# PHY_ETHERNET.net
KiCad netlist of a schematic drawn in Altium Designer
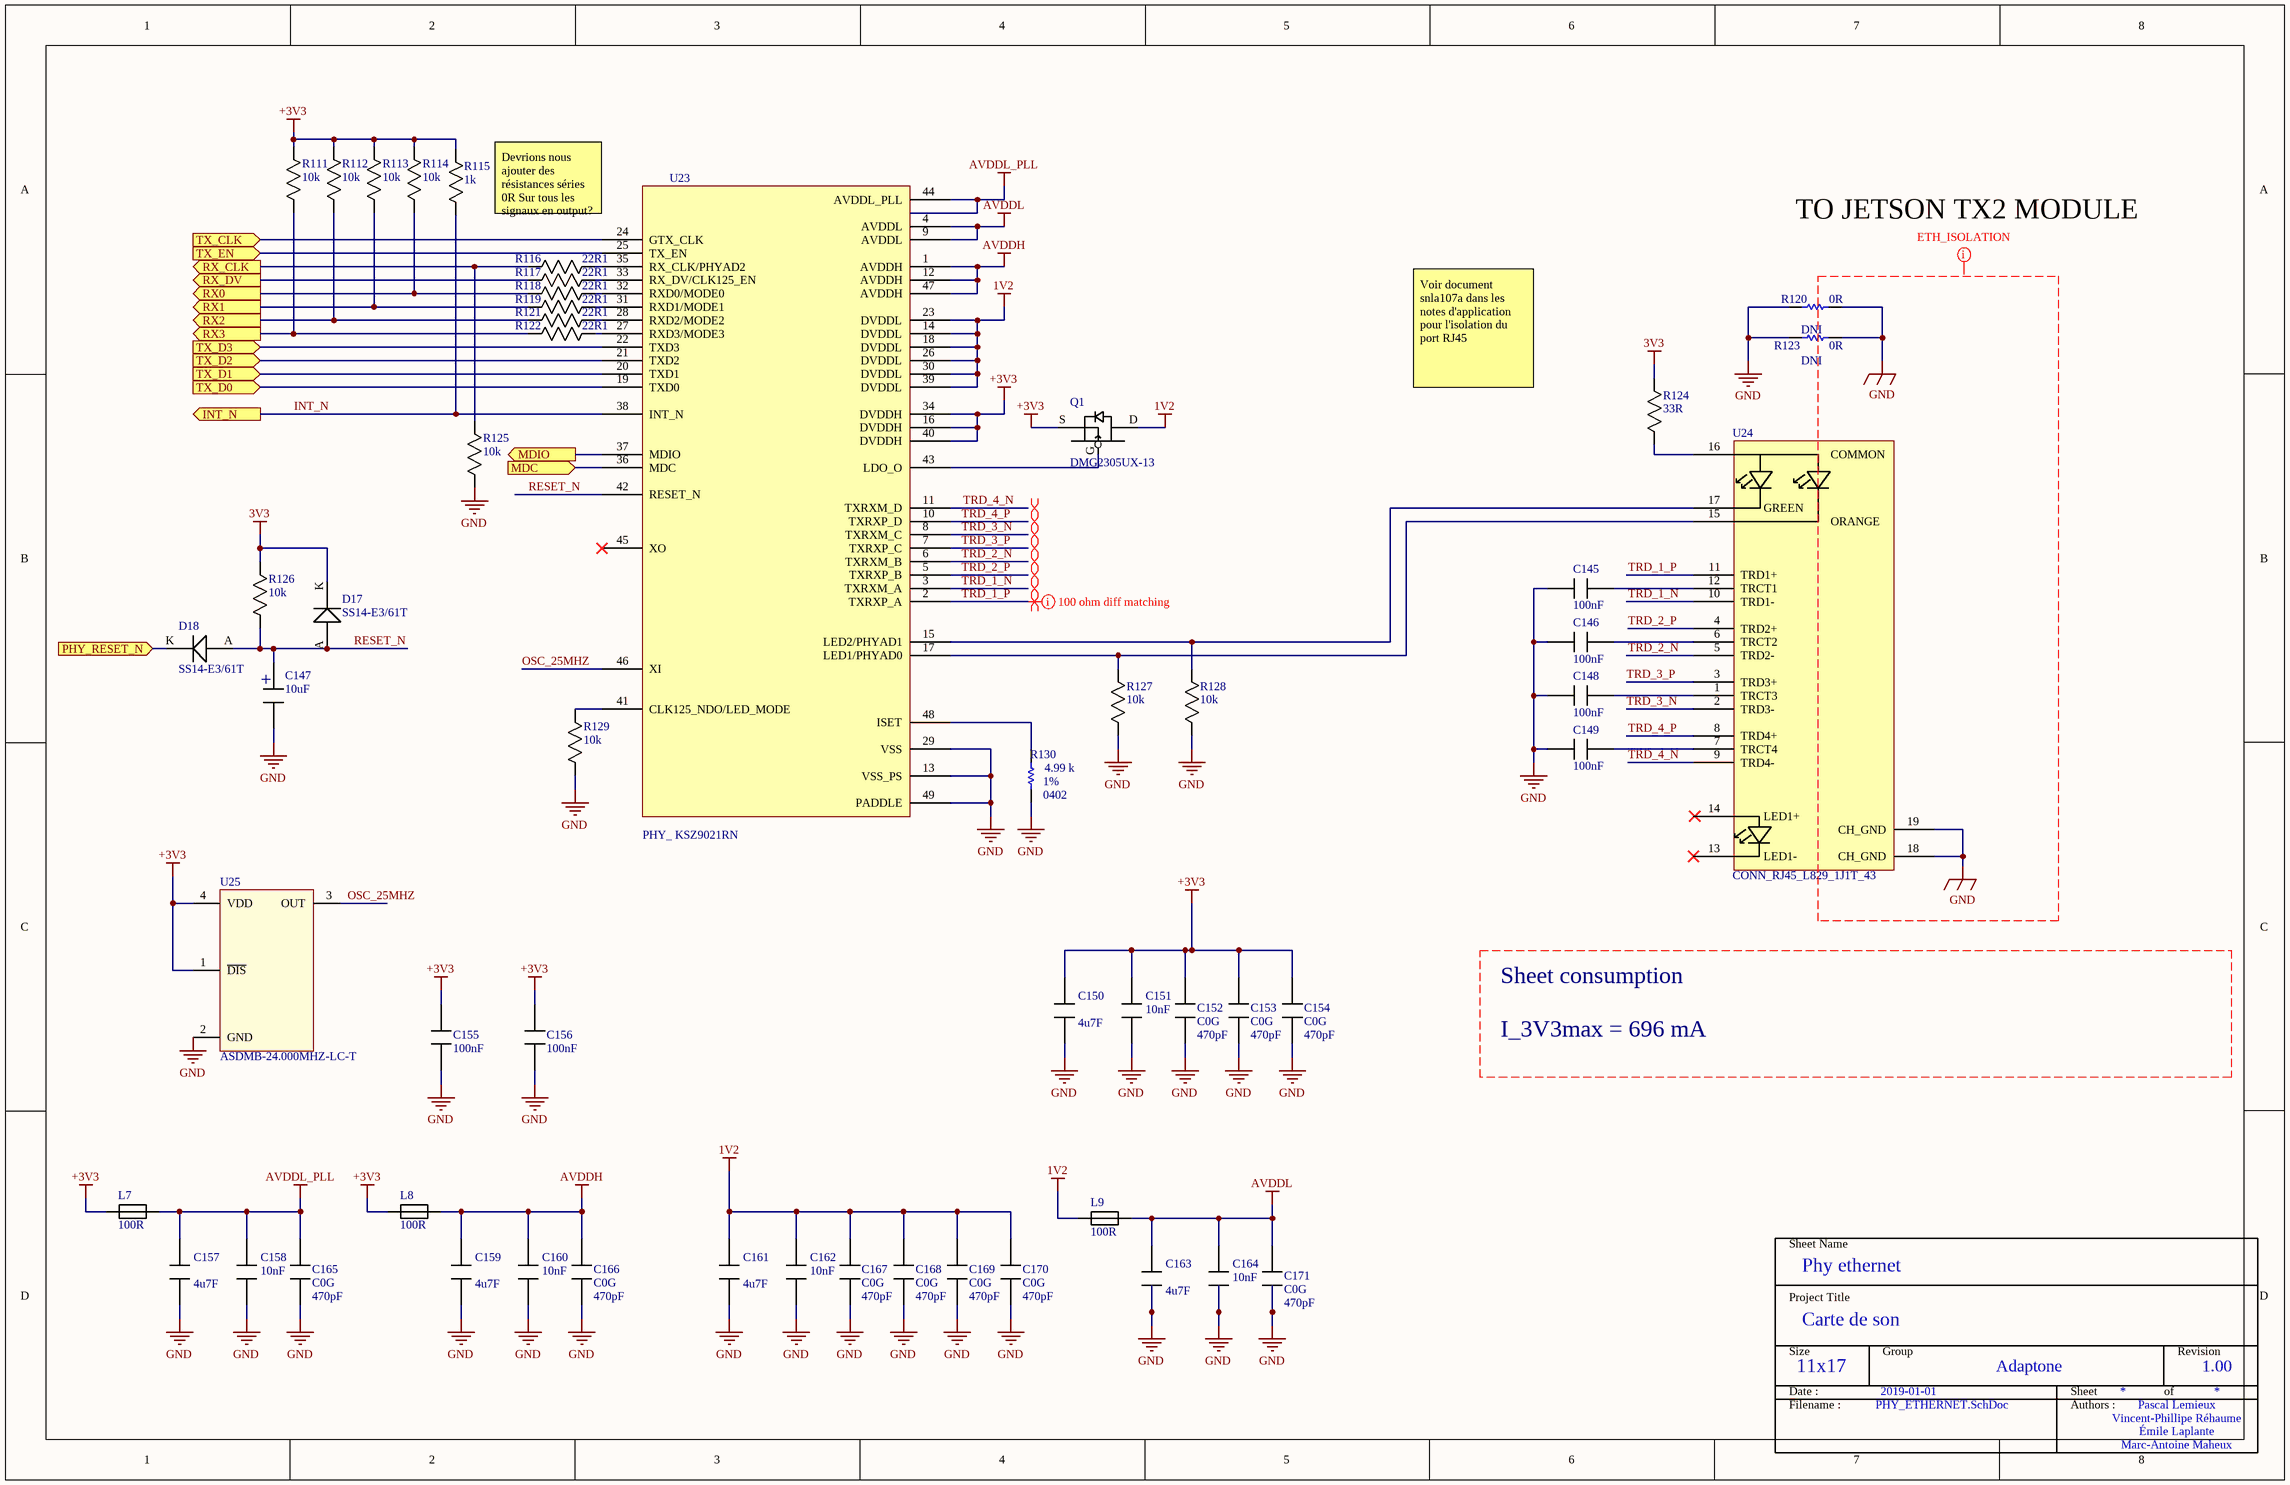
[diagram p0: PHY_ETHERNET.SchDoc]

(export (version "E")
  (design (tool "Eeschema 10.0.6"))
  (components
    (comp (ref "C145")
      (value "100nF")
      (footprint "0603")
      (description "Capacitor")
      (fields (field (name "MFG") "Samsung"))
      (libsource (lib "ADAPTONE_CARTE_DE_SON") (part "Capacitor"))
    )
    (comp (ref "C146")
      (value "100nF")
      (footprint "0603")
      (description "Capacitor")
      (fields (field (name "MFG") "Samsung"))
      (libsource (lib "ADAPTONE_CARTE_DE_SON") (part "Capacitor"))
    )
    (comp (ref "C147")
      (value "10uF")
      (footprint "CAP_RAD_SMD_DIA157")
      (description "Capacitor")
      (fields (field (name "MFG") "Nichicon") (field (name "Comment") "Capacitor_Polarized"))
      (libsource (lib "ADAPTONE_CARTE_DE_SON") (part "Capacitor_Polarized"))
    )
    (comp (ref "C148")
      (value "100nF")
      (footprint "0603")
      (description "Capacitor")
      (fields (field (name "MFG") "Samsung"))
      (libsource (lib "ADAPTONE_CARTE_DE_SON") (part "Capacitor"))
    )
    (comp (ref "C149")
      (value "100nF")
      (footprint "0603")
      (description "Capacitor")
      (fields (field (name "MFG") "Samsung"))
      (libsource (lib "ADAPTONE_CARTE_DE_SON") (part "Capacitor"))
    )
    (comp (ref "C150")
      (value "4u7F")
      (footprint "0805")
      (description "Capacitor")
      (fields (field (name "MFG") "Samsung"))
      (libsource (lib "ADAPTONE_CARTE_DE_SON") (part "Capacitor"))
    )
    (comp (ref "C151")
      (value "10nF")
      (footprint "0603")
      (description "Capacitor")
      (fields (field (name "MFG") "Murata"))
      (libsource (lib "ADAPTONE_CARTE_DE_SON") (part "Capacitor"))
    )
    (comp (ref "C152")
      (value "470pF")
      (footprint "0603")
      (description "Capacitor")
      (fields (field (name "MFG") "Samsung") (field (name "TYPE") "C0G"))
      (libsource (lib "ADAPTONE_CARTE_DE_SON") (part "Capacitor"))
    )
    (comp (ref "C153")
      (value "470pF")
      (footprint "0603")
      (description "Capacitor")
      (fields (field (name "MFG") "Samsung") (field (name "TYPE") "C0G"))
      (libsource (lib "ADAPTONE_CARTE_DE_SON") (part "Capacitor"))
    )
    (comp (ref "C154")
      (value "470pF")
      (footprint "0603")
      (description "Capacitor")
      (fields (field (name "MFG") "Samsung") (field (name "TYPE") "C0G"))
      (libsource (lib "ADAPTONE_CARTE_DE_SON") (part "Capacitor"))
    )
    (comp (ref "C155")
      (value "100nF")
      (footprint "0603")
      (description "Capacitor")
      (fields (field (name "MFG") "Samsung"))
      (libsource (lib "ADAPTONE_CARTE_DE_SON") (part "Capacitor"))
    )
    (comp (ref "C156")
      (value "100nF")
      (footprint "0603")
      (description "Capacitor")
      (fields (field (name "MFG") "Samsung"))
      (libsource (lib "ADAPTONE_CARTE_DE_SON") (part "Capacitor"))
    )
    (comp (ref "C157")
      (value "4u7F")
      (footprint "0805")
      (description "Capacitor")
      (fields (field (name "MFG") "Samsung"))
      (libsource (lib "ADAPTONE_CARTE_DE_SON") (part "Capacitor"))
    )
    (comp (ref "C158")
      (value "10nF")
      (footprint "0603")
      (description "Capacitor")
      (fields (field (name "MFG") "Murata"))
      (libsource (lib "ADAPTONE_CARTE_DE_SON") (part "Capacitor"))
    )
    (comp (ref "C159")
      (value "4u7F")
      (footprint "0805")
      (description "Capacitor")
      (fields (field (name "MFG") "Samsung"))
      (libsource (lib "ADAPTONE_CARTE_DE_SON") (part "Capacitor"))
    )
    (comp (ref "C160")
      (value "10nF")
      (footprint "0603")
      (description "Capacitor")
      (fields (field (name "MFG") "Murata"))
      (libsource (lib "ADAPTONE_CARTE_DE_SON") (part "Capacitor"))
    )
    (comp (ref "C161")
      (value "4u7F")
      (footprint "0805")
      (description "Capacitor")
      (fields (field (name "MFG") "Samsung"))
      (libsource (lib "ADAPTONE_CARTE_DE_SON") (part "Capacitor"))
    )
    (comp (ref "C162")
      (value "10nF")
      (footprint "0603")
      (description "Capacitor")
      (fields (field (name "MFG") "Murata"))
      (libsource (lib "ADAPTONE_CARTE_DE_SON") (part "Capacitor"))
    )
    (comp (ref "C163")
      (value "4u7F")
      (footprint "0805")
      (description "Capacitor")
      (fields (field (name "MFG") "Samsung"))
      (libsource (lib "ADAPTONE_CARTE_DE_SON") (part "Capacitor"))
    )
    (comp (ref "C164")
      (value "10nF")
      (footprint "0603")
      (description "Capacitor")
      (fields (field (name "MFG") "Murata"))
      (libsource (lib "ADAPTONE_CARTE_DE_SON") (part "Capacitor"))
    )
    (comp (ref "C165")
      (value "470pF")
      (footprint "0603")
      (description "Capacitor")
      (fields (field (name "MFG") "Samsung") (field (name "TYPE") "C0G"))
      (libsource (lib "ADAPTONE_CARTE_DE_SON") (part "Capacitor"))
    )
    (comp (ref "C166")
      (value "470pF")
      (footprint "0603")
      (description "Capacitor")
      (fields (field (name "MFG") "Samsung") (field (name "TYPE") "C0G"))
      (libsource (lib "ADAPTONE_CARTE_DE_SON") (part "Capacitor"))
    )
    (comp (ref "C167")
      (value "470pF")
      (footprint "0603")
      (description "Capacitor")
      (fields (field (name "MFG") "Samsung") (field (name "TYPE") "C0G"))
      (libsource (lib "ADAPTONE_CARTE_DE_SON") (part "Capacitor"))
    )
    (comp (ref "C168")
      (value "470pF")
      (footprint "0603")
      (description "Capacitor")
      (fields (field (name "MFG") "Samsung") (field (name "TYPE") "C0G"))
      (libsource (lib "ADAPTONE_CARTE_DE_SON") (part "Capacitor"))
    )
    (comp (ref "C169")
      (value "470pF")
      (footprint "0603")
      (description "Capacitor")
      (fields (field (name "MFG") "Samsung") (field (name "TYPE") "C0G"))
      (libsource (lib "ADAPTONE_CARTE_DE_SON") (part "Capacitor"))
    )
    (comp (ref "C170")
      (value "470pF")
      (footprint "0603")
      (description "Capacitor")
      (fields (field (name "MFG") "Samsung") (field (name "TYPE") "C0G"))
      (libsource (lib "ADAPTONE_CARTE_DE_SON") (part "Capacitor"))
    )
    (comp (ref "C171")
      (value "470pF")
      (footprint "0603")
      (description "Capacitor")
      (fields (field (name "MFG") "Samsung") (field (name "TYPE") "C0G"))
      (libsource (lib "ADAPTONE_CARTE_DE_SON") (part "Capacitor"))
    )
    (comp (ref "D17")
      (value "Diode")
      (footprint "DIODE_SMA")
      (fields (field (name "MFG") "Vishay") (field (name "MFG_PN") "SS14-E3/61T"))
      (libsource (lib "ADAPTONE_CARTE_DE_SON") (part "Diode"))
    )
    (comp (ref "D18")
      (value "Diode")
      (footprint "DIODE_SMA")
      (fields (field (name "MFG") "Vishay") (field (name "MFG_PN") "SS14-E3/61T"))
      (libsource (lib "ADAPTONE_CARTE_DE_SON") (part "Diode"))
    )
    (comp (ref "L7")
      (value "100R")
      (footprint "0603")
      (description "Ferrite")
      (fields (field (name "MFG") "Bourns"))
      (libsource (lib "ADAPTONE_CARTE_DE_SON") (part "Ferrite"))
    )
    (comp (ref "L8")
      (value "100R")
      (footprint "0603")
      (description "Ferrite")
      (fields (field (name "MFG") "Bourns"))
      (libsource (lib "ADAPTONE_CARTE_DE_SON") (part "Ferrite"))
    )
    (comp (ref "L9")
      (value "100R")
      (footprint "0603")
      (description "Ferrite")
      (fields (field (name "MFG") "Bourns"))
      (libsource (lib "ADAPTONE_CARTE_DE_SON") (part "Ferrite"))
    )
    (comp (ref "Q1")
      (value "MOSFET_P_GDS")
      (footprint "SOT23_GDS")
      (description "PMOS")
      (fields (field (name "MFG") "Diodes Incorporated") (field (name "MFG_PN") "DMG2305UX-13"))
      (libsource (lib "ADAPTONE_CARTE_DE_SON") (part "MOSFET_P_GDS"))
    )
    (comp (ref "R111")
      (value "10k")
      (footprint "0603")
      (description "Resistor")
      (fields (field (name "MFG") "Yageo"))
      (libsource (lib "ADAPTONE_CARTE_DE_SON") (part "Resistor"))
    )
    (comp (ref "R112")
      (value "10k")
      (footprint "0603")
      (description "Resistor")
      (fields (field (name "MFG") "Yageo"))
      (libsource (lib "ADAPTONE_CARTE_DE_SON") (part "Resistor"))
    )
    (comp (ref "R113")
      (value "10k")
      (footprint "0603")
      (description "Resistor")
      (fields (field (name "MFG") "Yageo"))
      (libsource (lib "ADAPTONE_CARTE_DE_SON") (part "Resistor"))
    )
    (comp (ref "R114")
      (value "10k")
      (footprint "0603")
      (description "Resistor")
      (fields (field (name "MFG") "Yageo"))
      (libsource (lib "ADAPTONE_CARTE_DE_SON") (part "Resistor"))
    )
    (comp (ref "R115")
      (value "1k")
      (footprint "0603")
      (description "Resistor")
      (fields (field (name "MFG") "Yageo"))
      (libsource (lib "ADAPTONE_CARTE_DE_SON") (part "Resistor"))
    )
    (comp (ref "R116")
      (value "22R1")
      (footprint "0402")
      (description "Resistor")
      (fields (field (name "MFG") "Yageo"))
      (libsource (lib "LIB_ADAPTONE_PASCAL_LEMIEUX") (part "Resistor"))
    )
    (comp (ref "R117")
      (value "22R1")
      (footprint "0402")
      (description "Resistor")
      (fields (field (name "MFG") "Yageo"))
      (libsource (lib "LIB_ADAPTONE_PASCAL_LEMIEUX") (part "Resistor"))
    )
    (comp (ref "R118")
      (value "22R1")
      (footprint "0402")
      (description "Resistor")
      (fields (field (name "MFG") "Yageo"))
      (libsource (lib "LIB_ADAPTONE_PASCAL_LEMIEUX") (part "Resistor"))
    )
    (comp (ref "R119")
      (value "22R1")
      (footprint "0402")
      (description "Resistor")
      (fields (field (name "MFG") "Yageo"))
      (libsource (lib "LIB_ADAPTONE_PASCAL_LEMIEUX") (part "Resistor"))
    )
    (comp (ref "R120")
      (value "0R")
      (footprint "RES_1206")
      (description "RES - 1206")
      (fields
        (field (name "MFG") "Stackpole Electronics Inc")
        (field (name "MFG PART NUMBER") "RMCF1206ZT0R00")
        (field (name "SPECIFICATION") "DNI")
        (field (name "CREATEDBY") "Jonathan Bouchard")
      )
      (libsource (lib "S7CAS_Lib2019_REV1_00") (part "RES - 1206"))
    )
    (comp (ref "R121")
      (value "22R1")
      (footprint "0402")
      (description "Resistor")
      (fields (field (name "MFG") "Yageo"))
      (libsource (lib "LIB_ADAPTONE_PASCAL_LEMIEUX") (part "Resistor"))
    )
    (comp (ref "R122")
      (value "22R1")
      (footprint "0402")
      (description "Resistor")
      (fields (field (name "MFG") "Yageo"))
      (libsource (lib "LIB_ADAPTONE_PASCAL_LEMIEUX") (part "Resistor"))
    )
    (comp (ref "R123")
      (value "0R")
      (footprint "RES_1206")
      (description "RES - 1206")
      (fields
        (field (name "MFG") "Stackpole Electronics Inc")
        (field (name "MFG PART NUMBER") "RMCF1206ZT0R00")
        (field (name "SPECIFICATION") "DNI")
        (field (name "CREATEDBY") "Jonathan Bouchard")
      )
      (libsource (lib "S7CAS_Lib2019_REV1_00") (part "RES - 1206"))
    )
    (comp (ref "R124")
      (value "33R")
      (footprint "0603")
      (description "Resistor")
      (fields (field (name "MFG") "Yageo"))
      (libsource (lib "ADAPTONE_CARTE_DE_SON") (part "Resistor"))
    )
    (comp (ref "R125")
      (value "10k")
      (footprint "0603")
      (description "Resistor")
      (fields (field (name "MFG") "Yageo"))
      (libsource (lib "ADAPTONE_CARTE_DE_SON") (part "Resistor"))
    )
    (comp (ref "R126")
      (value "10k")
      (footprint "0603")
      (description "Resistor")
      (fields (field (name "MFG") "Yageo"))
      (libsource (lib "ADAPTONE_CARTE_DE_SON") (part "Resistor"))
    )
    (comp (ref "R127")
      (value "10k")
      (footprint "0603")
      (description "Resistor")
      (fields (field (name "MFG") "Yageo"))
      (libsource (lib "ADAPTONE_CARTE_DE_SON") (part "Resistor"))
    )
    (comp (ref "R128")
      (value "10k")
      (footprint "0603")
      (description "Resistor")
      (fields (field (name "MFG") "Yageo"))
      (libsource (lib "ADAPTONE_CARTE_DE_SON") (part "Resistor"))
    )
    (comp (ref "R129")
      (value "10k")
      (footprint "0603")
      (description "Resistor")
      (fields (field (name "MFG") "Yageo"))
      (libsource (lib "ADAPTONE_CARTE_DE_SON") (part "Resistor"))
    )
    (comp (ref "R130")
      (value "4.99 k")
      (footprint "RES_0402")
      (description "RES - 0402")
      (fields
        (field (name "MFG") "Yageo")
        (field (name "MFG PART NUMBER") "RC0402FR-074K99L")
        (field (name "PACKAGE") "0402")
        (field (name "PRECISION") "1%")
        (field (name "CREATEDBY") "Jonathan Bouchard")
      )
      (libsource (lib "S7CAS_Lib2019_REV1_00") (part "RES - 0402"))
    )
    (comp (ref "U23")
      (value "PHY_ KSZ9021RN")
      (footprint "PHY_KSZ9021RN")
      (fields
        (field (name "MFG") "Microchip Technology")
        (field (name "MFG PART NUMBER") "KSZ9021RN")
        (field (name "CREATEDBY") "Emile Laplante")
        (field (name "VERIFIEDBY") "*")
      )
      (libsource (lib "LIB_ADAPTONE_EMILE_LAPLANTE") (part "PHY_ KSZ9021RN"))
    )
    (comp (ref "U24")
      (value "CONN_RJ45_L829_1J1T_43")
      (footprint "L829-1J1T-43")
      (fields
        (field (name "MFG") "Bel Fuse Inc.")
        (field (name "MFG PART NUMBER") "L829-1J1T-43")
        (field (name "CREATEDBY") "Emile Laplante")
        (field (name "VERIFIEDBY") "*")
      )
      (libsource (lib "LIB_ADAPTONE_EMILE_LAPLANTE") (part "CONN_RJ45_L829_1J1T_43"))
    )
    (comp (ref "U25")
      (value "OSC_ASDMB")
      (footprint "OSC_ADSMB")
      (description "Oscillator; 1V8 to 3V3")
      (fields (field (name "MFG") "Abracon") (field (name "MFG_PN") "ASDMB-24.000MHZ-LC-T"))
      (libsource (lib "ADAPTONE_CARTE_DE_SON") (part "OSC_ASDMB"))
    )
  )
  (nets
    (net (code "1") (name "+3V3") (class "Default")
      (node (ref "C150") (pin "1") (pintype "passive"))
      (node (ref "C151") (pin "1") (pintype "passive"))
      (node (ref "C152") (pin "2") (pintype "passive"))
      (node (ref "C153") (pin "2") (pintype "passive"))
      (node (ref "C154") (pin "2") (pintype "passive"))
      (node (ref "C155") (pin "1") (pintype "passive"))
      (node (ref "C156") (pin "1") (pintype "passive"))
      (node (ref "L7") (pin "1") (pintype "passive"))
      (node (ref "L8") (pin "1") (pintype "passive"))
      (node (ref "Q1") (pin "S") (pintype "passive"))
      (node (ref "R111") (pin "1") (pintype "passive"))
      (node (ref "R112") (pin "1") (pintype "passive"))
      (node (ref "R113") (pin "1") (pintype "passive"))
      (node (ref "R114") (pin "1") (pintype "passive"))
      (node (ref "R115") (pin "2") (pintype "passive"))
      (node (ref "U23") (pin "16") (pinfunction "DVDDH_16") (pintype "passive"))
      (node (ref "U23") (pin "34") (pinfunction "DVDDH_34") (pintype "passive"))
      (node (ref "U23") (pin "40") (pinfunction "DVDDH_40") (pintype "passive"))
      (node (ref "U25") (pin "1") (pinfunction "~{DIS}_1") (pintype "passive"))
      (node (ref "U25") (pin "4") (pinfunction "VDD_4") (pintype "passive"))
    )
    (net (code "2") (name "/INT_N") (class "Default")
      (node (ref "R115") (pin "1") (pintype "passive"))
      (node (ref "U23") (pin "38") (pinfunction "INT_N_38") (pintype "power_in"))
    )
    (net (code "3") (name "/MDC") (class "Default")
      (node (ref "U23") (pin "36") (pinfunction "MDC_36") (pintype "power_in"))
    )
    (net (code "4") (name "/MDIO") (class "Default")
      (node (ref "U23") (pin "37") (pinfunction "MDIO_37") (pintype "power_in"))
    )
    (net (code "5") (name "/OSC_25MHZ") (class "Default")
      (node (ref "U23") (pin "46") (pinfunction "XI_46") (pintype "power_in"))
      (node (ref "U25") (pin "3") (pinfunction "OUT_3") (pintype "passive"))
    )
    (net (code "6") (name "/PHY_RESET_N") (class "Default") (node (ref "D18") (pin "K") (pintype "passive")))
    (net (code "7") (name "/RESET_N") (class "Default")
      (node (ref "C147") (pin "+") (pintype "passive"))
      (node (ref "D17") (pin "A") (pintype "passive"))
      (node (ref "D18") (pin "A") (pintype "passive"))
      (node (ref "R126") (pin "1") (pintype "passive"))
      (node (ref "U23") (pin "42") (pinfunction "RESET_N_42") (pintype "power_in"))
    )
    (net (code "8") (name "/RX0") (class "Default")
      (node (ref "R114") (pin "2") (pintype "passive"))
      (node (ref "R118") (pin "1") (pintype "passive"))
    )
    (net (code "9") (name "/RX1") (class "Default")
      (node (ref "R113") (pin "2") (pintype "passive"))
      (node (ref "R119") (pin "1") (pintype "passive"))
    )
    (net (code "10") (name "/RX2") (class "Default")
      (node (ref "R112") (pin "2") (pintype "passive"))
      (node (ref "R121") (pin "1") (pintype "passive"))
    )
    (net (code "11") (name "/RX3") (class "Default")
      (node (ref "R111") (pin "2") (pintype "passive"))
      (node (ref "R122") (pin "1") (pintype "passive"))
    )
    (net (code "12") (name "/RX_CLK") (class "Default")
      (node (ref "R116") (pin "1") (pintype "passive"))
      (node (ref "R125") (pin "1") (pintype "passive"))
    )
    (net (code "13") (name "/RX_DV") (class "Default") (node (ref "R117") (pin "1") (pintype "passive")))
    (net (code "14") (name "/TRD_1_N") (class "Default")
      (node (ref "U23") (pin "3") (pinfunction "TXRXM_A_3") (pintype "power_in"))
      (node (ref "U24") (pin "10") (pinfunction "TRD1-_10") (pintype "power_in"))
    )
    (net (code "15") (name "/TRD_1_P") (class "Default")
      (node (ref "U23") (pin "2") (pinfunction "TXRXP_A_2") (pintype "power_in"))
      (node (ref "U24") (pin "11") (pinfunction "TRD1+_11") (pintype "power_in"))
    )
    (net (code "16") (name "/TRD_2_N") (class "Default")
      (node (ref "U23") (pin "6") (pinfunction "TXRXM_B_6") (pintype "power_in"))
      (node (ref "U24") (pin "5") (pinfunction "TRD2-_5") (pintype "power_in"))
    )
    (net (code "17") (name "/TRD_2_P") (class "Default")
      (node (ref "U23") (pin "5") (pinfunction "TXRXP_B_5") (pintype "power_in"))
      (node (ref "U24") (pin "4") (pinfunction "TRD2+_4") (pintype "power_in"))
    )
    (net (code "18") (name "/TRD_3_N") (class "Default")
      (node (ref "U23") (pin "8") (pinfunction "TXRXM_C_8") (pintype "power_in"))
      (node (ref "U24") (pin "2") (pinfunction "TRD3-_2") (pintype "power_in"))
    )
    (net (code "19") (name "/TRD_3_P") (class "Default")
      (node (ref "U23") (pin "7") (pinfunction "TXRXP_C_7") (pintype "power_in"))
      (node (ref "U24") (pin "3") (pinfunction "TRD3+_3") (pintype "power_in"))
    )
    (net (code "20") (name "/TRD_4_N") (class "Default")
      (node (ref "U23") (pin "11") (pinfunction "TXRXM_D_11") (pintype "power_in"))
      (node (ref "U24") (pin "9") (pinfunction "TRD4-_9") (pintype "power_in"))
    )
    (net (code "21") (name "/TRD_4_P") (class "Default")
      (node (ref "U23") (pin "10") (pinfunction "TXRXP_D_10") (pintype "power_in"))
      (node (ref "U24") (pin "8") (pinfunction "TRD4+_8") (pintype "power_in"))
    )
    (net (code "22") (name "/TX_CLK") (class "Default")
      (node (ref "U23") (pin "24") (pinfunction "GTX_CLK_24") (pintype "power_in"))
    )
    (net (code "23") (name "/TX_D0") (class "Default")
      (node (ref "U23") (pin "19") (pinfunction "TXD0_19") (pintype "power_in"))
    )
    (net (code "24") (name "/TX_D1") (class "Default")
      (node (ref "U23") (pin "20") (pinfunction "TXD1_20") (pintype "power_in"))
    )
    (net (code "25") (name "/TX_D2") (class "Default")
      (node (ref "U23") (pin "21") (pinfunction "TXD2_21") (pintype "power_in"))
    )
    (net (code "26") (name "/TX_D3") (class "Default")
      (node (ref "U23") (pin "22") (pinfunction "TXD3_22") (pintype "power_in"))
    )
    (net (code "27") (name "/TX_EN") (class "Default")
      (node (ref "U23") (pin "25") (pinfunction "TX_EN_25") (pintype "power_in"))
    )
    (net (code "28") (name "1V2") (class "Default")
      (node (ref "C161") (pin "1") (pintype "passive"))
      (node (ref "C162") (pin "1") (pintype "passive"))
      (node (ref "C167") (pin "2") (pintype "passive"))
      (node (ref "C168") (pin "2") (pintype "passive"))
      (node (ref "C169") (pin "2") (pintype "passive"))
      (node (ref "C170") (pin "2") (pintype "passive"))
      (node (ref "L9") (pin "1") (pintype "passive"))
      (node (ref "Q1") (pin "D") (pintype "passive"))
      (node (ref "U23") (pin "14") (pinfunction "DVDDL_14") (pintype "passive"))
      (node (ref "U23") (pin "18") (pinfunction "DVDDL_18") (pintype "passive"))
      (node (ref "U23") (pin "23") (pinfunction "DVDDL_23") (pintype "passive"))
      (node (ref "U23") (pin "26") (pinfunction "DVDDL_26") (pintype "passive"))
      (node (ref "U23") (pin "30") (pinfunction "DVDDL_30") (pintype "passive"))
      (node (ref "U23") (pin "39") (pinfunction "DVDDL_39") (pintype "passive"))
    )
    (net (code "29") (name "3V3") (class "Default")
      (node (ref "D17") (pin "K") (pintype "passive"))
      (node (ref "R124") (pin "2") (pintype "passive"))
      (node (ref "R126") (pin "2") (pintype "passive"))
    )
    (net (code "30") (name "AVDDH") (class "Default")
      (node (ref "C159") (pin "1") (pintype "passive"))
      (node (ref "C160") (pin "1") (pintype "passive"))
      (node (ref "C166") (pin "2") (pintype "passive"))
      (node (ref "L8") (pin "2") (pintype "passive"))
      (node (ref "U23") (pin "1") (pinfunction "AVDDH_1") (pintype "passive"))
      (node (ref "U23") (pin "12") (pinfunction "AVDDH_12") (pintype "passive"))
      (node (ref "U23") (pin "47") (pinfunction "AVDDH_47") (pintype "passive"))
    )
    (net (code "31") (name "AVDDL") (class "Default")
      (node (ref "C163") (pin "1") (pintype "passive"))
      (node (ref "C164") (pin "1") (pintype "passive"))
      (node (ref "C171") (pin "2") (pintype "passive"))
      (node (ref "L9") (pin "2") (pintype "passive"))
      (node (ref "U23") (pin "4") (pinfunction "AVDDL_4") (pintype "passive"))
      (node (ref "U23") (pin "9") (pinfunction "AVDDL_9") (pintype "passive"))
    )
    (net (code "32") (name "AVDDL_PLL") (class "Default")
      (node (ref "C157") (pin "1") (pintype "passive"))
      (node (ref "C158") (pin "1") (pintype "passive"))
      (node (ref "C165") (pin "2") (pintype "passive"))
      (node (ref "L7") (pin "2") (pintype "passive"))
      (node (ref "U23") (pin "44") (pinfunction "AVDDL_PLL_44") (pintype "passive"))
    )
    (net (code "33") (name "GND") (class "Default")
      (node (ref "C145") (pin "2") (pintype "passive"))
      (node (ref "C146") (pin "2") (pintype "passive"))
      (node (ref "C147") (pin "-") (pintype "passive"))
      (node (ref "C148") (pin "2") (pintype "passive"))
      (node (ref "C149") (pin "2") (pintype "passive"))
      (node (ref "C150") (pin "2") (pintype "passive"))
      (node (ref "C151") (pin "2") (pintype "passive"))
      (node (ref "C152") (pin "1") (pintype "passive"))
      (node (ref "C153") (pin "1") (pintype "passive"))
      (node (ref "C154") (pin "1") (pintype "passive"))
      (node (ref "C155") (pin "2") (pintype "passive"))
      (node (ref "C156") (pin "2") (pintype "passive"))
      (node (ref "C157") (pin "2") (pintype "passive"))
      (node (ref "C158") (pin "2") (pintype "passive"))
      (node (ref "C159") (pin "2") (pintype "passive"))
      (node (ref "C160") (pin "2") (pintype "passive"))
      (node (ref "C161") (pin "2") (pintype "passive"))
      (node (ref "C162") (pin "2") (pintype "passive"))
      (node (ref "C163") (pin "2") (pintype "passive"))
      (node (ref "C164") (pin "2") (pintype "passive"))
      (node (ref "C165") (pin "1") (pintype "passive"))
      (node (ref "C166") (pin "1") (pintype "passive"))
      (node (ref "C167") (pin "1") (pintype "passive"))
      (node (ref "C168") (pin "1") (pintype "passive"))
      (node (ref "C169") (pin "1") (pintype "passive"))
      (node (ref "C170") (pin "1") (pintype "passive"))
      (node (ref "C171") (pin "1") (pintype "passive"))
      (node (ref "R120") (pin "1") (pinfunction "1_1") (pintype "passive"))
      (node (ref "R120") (pin "2") (pinfunction "2_2") (pintype "passive"))
      (node (ref "R123") (pin "1") (pinfunction "1_1") (pintype "passive"))
      (node (ref "R123") (pin "2") (pinfunction "2_2") (pintype "passive"))
      (node (ref "R125") (pin "2") (pintype "passive"))
      (node (ref "R127") (pin "2") (pintype "passive"))
      (node (ref "R128") (pin "2") (pintype "passive"))
      (node (ref "R129") (pin "2") (pintype "passive"))
      (node (ref "R130") (pin "1") (pinfunction "1_1") (pintype "passive"))
      (node (ref "U23") (pin "13") (pinfunction "VSS_PS_13") (pintype "passive"))
      (node (ref "U23") (pin "29") (pinfunction "VSS_29") (pintype "passive"))
      (node (ref "U23") (pin "49") (pinfunction "PADDLE_49") (pintype "passive"))
      (node (ref "U24") (pin "18") (pinfunction "CH_GND_18") (pintype "passive"))
      (node (ref "U24") (pin "19") (pinfunction "CH_GND_19") (pintype "passive"))
      (node (ref "U25") (pin "2") (pinfunction "GND_2") (pintype "passive"))
    )
    (net (code "34") (name "Net-(U23-CLK125_NDO{slash}LED_MODE)") (class "Default")
      (node (ref "R129") (pin "1") (pintype "passive"))
      (node (ref "U23") (pin "41") (pinfunction "CLK125_NDO/LED_MODE_41") (pintype "power_in"))
    )
    (net (code "35") (name "Net-(U23-ISET)") (class "Default")
      (node (ref "R130") (pin "2") (pinfunction "2_2") (pintype "passive"))
      (node (ref "U23") (pin "48") (pinfunction "ISET_48") (pintype "passive"))
    )
    (net (code "36") (name "Net-(U23-LDO_O)") (class "Default")
      (node (ref "Q1") (pin "G") (pintype "passive"))
      (node (ref "U23") (pin "43") (pinfunction "LDO_O_43") (pintype "passive"))
    )
    (net (code "37") (name "Net-(U23-LED1{slash}PHYAD0)") (class "Default")
      (node (ref "R127") (pin "1") (pintype "passive"))
      (node (ref "U23") (pin "17") (pinfunction "LED1/PHYAD0_17") (pintype "power_in"))
      (node (ref "U24") (pin "15") (pinfunction "ORANGE_15") (pintype "passive"))
    )
    (net (code "38") (name "Net-(U23-LED2{slash}PHYAD1)") (class "Default")
      (node (ref "R128") (pin "1") (pintype "passive"))
      (node (ref "U23") (pin "15") (pinfunction "LED2/PHYAD1_15") (pintype "power_in"))
      (node (ref "U24") (pin "17") (pinfunction "GREEN_17") (pintype "passive"))
    )
    (net (code "39") (name "Net-(U23-RXD0{slash}MODE0)") (class "Default")
      (node (ref "R118") (pin "2") (pintype "passive"))
      (node (ref "U23") (pin "32") (pinfunction "RXD0/MODE0_32") (pintype "power_in"))
    )
    (net (code "40") (name "Net-(U23-RXD1{slash}MODE1)") (class "Default")
      (node (ref "R119") (pin "2") (pintype "passive"))
      (node (ref "U23") (pin "31") (pinfunction "RXD1/MODE1_31") (pintype "power_in"))
    )
    (net (code "41") (name "Net-(U23-RXD2{slash}MODE2)") (class "Default")
      (node (ref "R121") (pin "2") (pintype "passive"))
      (node (ref "U23") (pin "28") (pinfunction "RXD2/MODE2_28") (pintype "power_in"))
    )
    (net (code "42") (name "Net-(U23-RXD3{slash}MODE3)") (class "Default")
      (node (ref "R122") (pin "2") (pintype "passive"))
      (node (ref "U23") (pin "27") (pinfunction "RXD3/MODE3_27") (pintype "power_in"))
    )
    (net (code "43") (name "Net-(U23-RX_CLK{slash}PHYAD2)") (class "Default")
      (node (ref "R116") (pin "2") (pintype "passive"))
      (node (ref "U23") (pin "35") (pinfunction "RX_CLK/PHYAD2_35") (pintype "power_in"))
    )
    (net (code "44") (name "Net-(U23-RX_DV{slash}CLK125_EN)") (class "Default")
      (node (ref "R117") (pin "2") (pintype "passive"))
      (node (ref "U23") (pin "33") (pinfunction "RX_DV/CLK125_EN_33") (pintype "power_in"))
    )
    (net (code "45") (name "Net-(U24-COMMON)") (class "Default")
      (node (ref "R124") (pin "1") (pintype "passive"))
      (node (ref "U24") (pin "16") (pinfunction "COMMON_16") (pintype "passive"))
    )
    (net (code "46") (name "Net-(U24-TRCT1)") (class "Default")
      (node (ref "C145") (pin "1") (pintype "passive"))
      (node (ref "U24") (pin "12") (pinfunction "TRCT1_12") (pintype "power_in"))
    )
    (net (code "47") (name "Net-(U24-TRCT2)") (class "Default")
      (node (ref "C146") (pin "1") (pintype "passive"))
      (node (ref "U24") (pin "6") (pinfunction "TRCT2_6") (pintype "power_in"))
    )
    (net (code "48") (name "Net-(U24-TRCT3)") (class "Default")
      (node (ref "C148") (pin "1") (pintype "passive"))
      (node (ref "U24") (pin "1") (pinfunction "TRCT3_1") (pintype "power_in"))
    )
    (net (code "49") (name "Net-(U24-TRCT4)") (class "Default")
      (node (ref "C149") (pin "1") (pintype "passive"))
      (node (ref "U24") (pin "7") (pinfunction "TRCT4_7") (pintype "power_in"))
    )
    (net (code "50") (name "unconnected-(U23-XO-Pad45)") (class "Default")
      (node (ref "U23") (pin "45") (pinfunction "XO_45") (pintype "power_in+no_connect"))
    )
    (net (code "51") (name "unconnected-(U24-LED1+-Pad14)") (class "Default")
      (node (ref "U24") (pin "14") (pinfunction "LED1+_14") (pintype "passive"))
    )
    (net (code "52") (name "unconnected-(U24-LED1--Pad13)") (class "Default")
      (node (ref "U24") (pin "13") (pinfunction "LED1-_13") (pintype "passive+no_connect"))
    )
  )
)
